# ADC_Breakout.net
KiCad netlist of a schematic drawn in Altium Designer
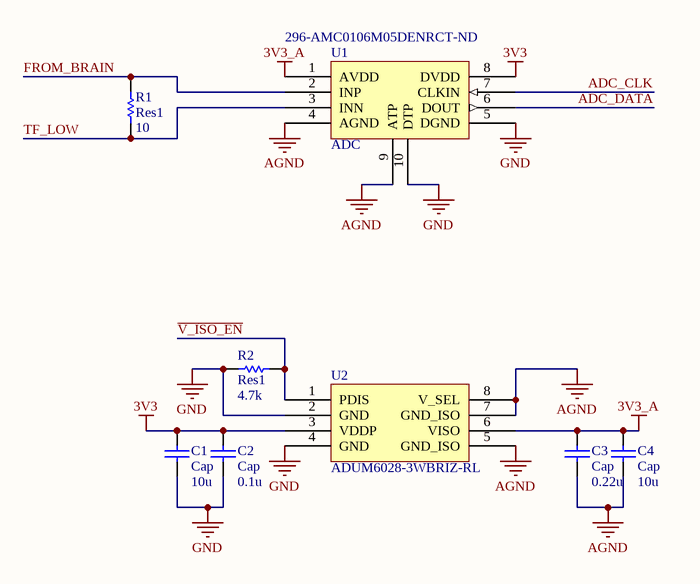
[diagram p0: ADC_Breakout.SchDoc]

(export (version "E")
  (design (tool "Eeschema 10.0.6"))
  (components
    (comp (ref "C1")
      (value "Cap")
      (footprint "CAPC1608X05N")
      (description "Capacitor")
      (fields (field (name "ALTIUM_VALUE") "10u") (field (name "PUBLISHER") "Altium Limited"))
      (libsource (lib "Miscellaneous Devices") (part "Cap"))
    )
    (comp (ref "C2")
      (value "Cap")
      (footprint "CAPC1608X05N")
      (description "Capacitor")
      (fields (field (name "ALTIUM_VALUE") "0.1u") (field (name "PUBLISHER") "Altium Limited"))
      (libsource (lib "Miscellaneous Devices") (part "Cap"))
    )
    (comp (ref "C3")
      (value "Cap")
      (footprint "CAPC1608X05N")
      (description "Capacitor")
      (fields (field (name "ALTIUM_VALUE") "0.22u") (field (name "PUBLISHER") "Altium Limited"))
      (libsource (lib "Miscellaneous Devices") (part "Cap"))
    )
    (comp (ref "C4")
      (value "Cap")
      (footprint "CAPC1608X05N")
      (description "Capacitor")
      (fields (field (name "ALTIUM_VALUE") "10u") (field (name "PUBLISHER") "Altium Limited"))
      (libsource (lib "Miscellaneous Devices") (part "Cap"))
    )
    (comp (ref "R1")
      (value "Res1")
      (footprint "PcbLib1:0402_Res")
      (description "Resistor")
      (fields (field (name "ALTIUM_VALUE") "10") (field (name "PUBLISHER") "Altium Limited"))
      (libsource (lib "Miscellaneous Devices") (part "Res1"))
    )
    (comp (ref "R2")
      (value "Res1")
      (footprint "0402_Res")
      (description "Resistor")
      (fields (field (name "ALTIUM_VALUE") "4.7k") (field (name "PUBLISHER") "Altium Limited"))
      (libsource (lib "Miscellaneous Devices") (part "Res1"))
    )
    (comp (ref "U1")
      (value "ADC")
      (footprint "PcbLib1:SON65P350X100_HS-9N")
      (fields (field (name "SUPPLIER PART NUMBER 1") "296-AMC0106M05DENRCT-ND"))
      (libsource (lib "Brain_Stim_Lib") (part "ADC"))
    )
    (comp (ref "U2")
      (value "ADUM6028-3WBRIZ-RL")
      (footprint "PcbLib1:ADUM6028-3WBRIZ-RL")
      (libsource (lib "Brain_Stim_Lib") (part "ADUM6028-3WBRIZ-RL"))
    )
  )
  (nets
    (net (code "1") (name "/ADC_CLK") (class "Default")
      (node (ref "U1") (pin "7") (pinfunction "CLKIN_7") (pintype "input"))
    )
    (net (code "2") (name "/ADC_DATA") (class "Default")
      (node (ref "U1") (pin "6") (pinfunction "DOUT_6") (pintype "output"))
    )
    (net (code "3") (name "/FROM_BRAIN") (class "Default")
      (node (ref "R1") (pin "1") (pinfunction "1_1") (pintype "passive"))
      (node (ref "U1") (pin "2") (pinfunction "INP_2") (pintype "passive"))
    )
    (net (code "4") (name "/TF_LOW") (class "Default")
      (node (ref "R1") (pin "2") (pinfunction "2_2") (pintype "passive"))
      (node (ref "U1") (pin "3") (pinfunction "INN_3") (pintype "passive"))
    )
    (net (code "5") (name "/~{V_ISO_EN}") (class "Default")
      (node (ref "R2") (pin "2") (pinfunction "2_2") (pintype "passive"))
      (node (ref "U2") (pin "1") (pinfunction "PDIS_1") (pintype "passive"))
    )
    (net (code "6") (name "3V3") (class "Default")
      (node (ref "C1") (pin "2") (pinfunction "2_2") (pintype "passive"))
      (node (ref "C2") (pin "2") (pinfunction "2_2") (pintype "passive"))
      (node (ref "U1") (pin "8") (pinfunction "DVDD_8") (pintype "passive"))
      (node (ref "U2") (pin "3") (pinfunction "VDDP_3") (pintype "passive"))
    )
    (net (code "7") (name "3V3_A") (class "Default")
      (node (ref "C3") (pin "2") (pinfunction "2_2") (pintype "passive"))
      (node (ref "C4") (pin "2") (pinfunction "2_2") (pintype "passive"))
      (node (ref "U1") (pin "1") (pinfunction "AVDD_1") (pintype "passive"))
      (node (ref "U2") (pin "6") (pinfunction "VISO_6") (pintype "passive"))
    )
    (net (code "8") (name "AGND") (class "Default")
      (node (ref "C3") (pin "1") (pinfunction "1_1") (pintype "passive"))
      (node (ref "C4") (pin "1") (pinfunction "1_1") (pintype "passive"))
      (node (ref "U1") (pin "4") (pinfunction "AGND_4") (pintype "passive"))
      (node (ref "U1") (pin "9") (pinfunction "ATP_9") (pintype "passive"))
      (node (ref "U2") (pin "5") (pinfunction "GND_ISO_5") (pintype "passive"))
      (node (ref "U2") (pin "7") (pinfunction "GND_ISO_7") (pintype "passive"))
      (node (ref "U2") (pin "8") (pinfunction "V_SEL_8") (pintype "passive"))
    )
    (net (code "9") (name "GND") (class "Default")
      (node (ref "C1") (pin "1") (pinfunction "1_1") (pintype "passive"))
      (node (ref "C2") (pin "1") (pinfunction "1_1") (pintype "passive"))
      (node (ref "R2") (pin "1") (pinfunction "1_1") (pintype "passive"))
      (node (ref "U1") (pin "10") (pinfunction "DTP_10") (pintype "passive"))
      (node (ref "U1") (pin "5") (pinfunction "DGND_5") (pintype "passive"))
      (node (ref "U2") (pin "2") (pinfunction "GND_2") (pintype "passive"))
      (node (ref "U2") (pin "4") (pinfunction "GND_4") (pintype "passive"))
    )
  )
)
